# dv_analog_interface_ch_old.net
KiCad netlist of a schematic drawn in Altium Designer
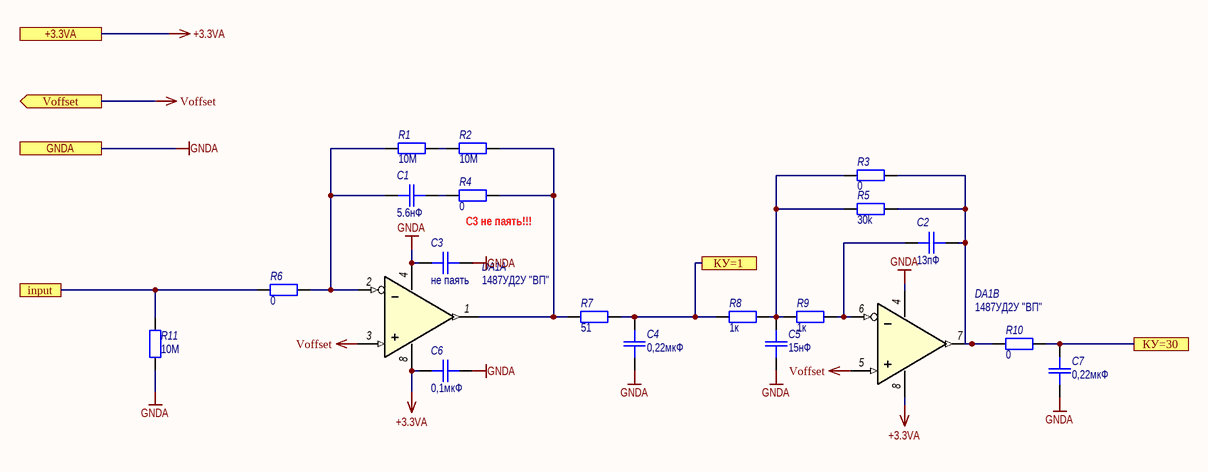
[diagram p0: dv_analog_interface_ch_old.SchDoc]

(export (version "E")
  (design (tool "Eeschema 10.0.6"))
  (components
    (comp (ref "C1")
      (value "5.6нФ")
      (footprint "SMD_C0805")
      (description "Capacitor")
      (fields (field (name "Comment") "K10-79"))
      (libsource (lib "Passive") (part "Capacitor"))
    )
    (comp (ref "C2")
      (value "13пФ")
      (footprint "SMD_C0805")
      (description "Capacitor")
      (fields (field (name "Comment") "K10-79"))
      (libsource (lib "Passive") (part "Capacitor"))
    )
    (comp (ref "C3")
      (value "не паять")
      (footprint "SMD_C0805")
      (description "Capacitor")
      (fields (field (name "Comment") "K10-79"))
      (libsource (lib "Passive") (part "Capacitor"))
    )
    (comp (ref "C4")
      (value "0,22мкФ")
      (footprint "SMD_C0805")
      (description "Capacitor")
      (fields (field (name "Comment") "K10-79"))
      (libsource (lib "Passive") (part "Capacitor"))
    )
    (comp (ref "C5")
      (value "15нФ")
      (footprint "SMD_C0805")
      (description "Capacitor")
      (fields (field (name "Comment") "K10-79"))
      (libsource (lib "Passive") (part "Capacitor"))
    )
    (comp (ref "C6")
      (value "0,1мкФ")
      (footprint "SMD_C0805")
      (description "Capacitor")
      (fields (field (name "Comment") "K10-79"))
      (libsource (lib "Passive") (part "Capacitor"))
    )
    (comp (ref "C7")
      (value "0,22мкФ")
      (footprint "SMD_C0805")
      (description "Capacitor")
      (fields (field (name "Comment") "K10-79"))
      (libsource (lib "Passive") (part "Capacitor"))
    )
    (comp (ref "DA1")
      (value "1487UD2U")
      (footprint "HO2.8-1B")
      (description "Сдвоенный операционный усилитель")
      (fields (field (name "НАИМЕНОВАНИЕ") "1487УД2У \"ВП\""))
      (libsource (lib "1487UD2U") (part "1487UD2U"))
    )
    (comp (ref "R1")
      (value "10M")
      (footprint "SMD_0805")
      (description "Resistor")
      (fields (field (name "Comment") "OSM R1-12"))
      (libsource (lib "Passive") (part "Resistor"))
    )
    (comp (ref "R2")
      (value "10M")
      (footprint "SMD_0805")
      (description "Resistor")
      (fields (field (name "Comment") "OSM R1-12"))
      (libsource (lib "Passive") (part "Resistor"))
    )
    (comp (ref "R3")
      (value "0")
      (footprint "SMD_0805")
      (description "Resistor")
      (fields (field (name "Comment") "OSM R1-12"))
      (libsource (lib "Passive") (part "Resistor"))
    )
    (comp (ref "R4")
      (value "0")
      (footprint "SMD_0805")
      (description "Resistor")
      (fields (field (name "Comment") "OSM R1-12"))
      (libsource (lib "Passive") (part "Resistor"))
    )
    (comp (ref "R5")
      (value "30k")
      (footprint "SMD_0805")
      (description "Resistor")
      (fields (field (name "Comment") "OSM R1-12"))
      (libsource (lib "Passive") (part "Resistor"))
    )
    (comp (ref "R6")
      (value "0")
      (footprint "SMD_0805")
      (description "Resistor")
      (fields (field (name "Comment") "OSM R1-12"))
      (libsource (lib "Passive") (part "Resistor"))
    )
    (comp (ref "R7")
      (value "51")
      (footprint "SMD_0805")
      (description "Resistor")
      (fields (field (name "Comment") "OSM R1-12"))
      (libsource (lib "Passive") (part "Resistor"))
    )
    (comp (ref "R8")
      (value "1к")
      (footprint "SMD_0805")
      (description "Resistor")
      (fields (field (name "Comment") "OSM R1-12"))
      (libsource (lib "Passive") (part "Resistor"))
    )
    (comp (ref "R9")
      (value "1к")
      (footprint "SMD_0805")
      (description "Resistor")
      (fields (field (name "Comment") "OSM R1-12"))
      (libsource (lib "Passive") (part "Resistor"))
    )
    (comp (ref "R10")
      (value "0")
      (footprint "SMD_0805")
      (description "Resistor")
      (fields (field (name "Comment") "OSM R1-12"))
      (libsource (lib "Passive") (part "Resistor"))
    )
    (comp (ref "R11")
      (value "10M")
      (footprint "SMD_0805")
      (description "Resistor")
      (fields (field (name "Comment") "OSM R1-12"))
      (libsource (lib "") (part "Resistor_1"))
    )
  )
  (nets
    (net (code "1") (name "+3.3VA") (class "Default")
      (node (ref "C6") (pin "1") (pinfunction "1_1") (pintype "passive"))
      (node (ref "DA1") (pin "8") (pinfunction "Vss+_8") (pintype "passive"))
    )
    (net (code "2") (name "/input") (class "Default")
      (node (ref "R11") (pin "2") (pinfunction "2_2") (pintype "passive"))
      (node (ref "R6") (pin "1") (pinfunction "1_1") (pintype "passive"))
    )
    (net (code "3") (name "/КУ=1") (class "Default")
      (node (ref "C4") (pin "2") (pinfunction "2_2") (pintype "passive"))
      (node (ref "R7") (pin "2") (pinfunction "2_2") (pintype "passive"))
      (node (ref "R8") (pin "1") (pinfunction "1_1") (pintype "passive"))
    )
    (net (code "4") (name "/КУ=30") (class "Default")
      (node (ref "C7") (pin "2") (pinfunction "2_2") (pintype "passive"))
      (node (ref "R10") (pin "2") (pinfunction "2_2") (pintype "passive"))
    )
    (net (code "5") (name "GNDA") (class "Default")
      (node (ref "C3") (pin "1") (pinfunction "1_1") (pintype "passive"))
      (node (ref "C3") (pin "2") (pinfunction "2_2") (pintype "passive"))
      (node (ref "C4") (pin "1") (pinfunction "1_1") (pintype "passive"))
      (node (ref "C5") (pin "1") (pinfunction "1_1") (pintype "passive"))
      (node (ref "C6") (pin "2") (pinfunction "2_2") (pintype "passive"))
      (node (ref "C7") (pin "1") (pinfunction "1_1") (pintype "passive"))
      (node (ref "DA1") (pin "4") (pinfunction "Vss-_4") (pintype "passive"))
      (node (ref "R11") (pin "1") (pinfunction "1_1") (pintype "passive"))
    )
    (net (code "6") (name "Net-(C1-Pad2)") (class "Default")
      (node (ref "C1") (pin "2") (pinfunction "2_2") (pintype "passive"))
      (node (ref "R4") (pin "1") (pinfunction "1_1") (pintype "passive"))
    )
    (net (code "7") (name "Net-(C5-Pad2)") (class "Default")
      (node (ref "C5") (pin "2") (pinfunction "2_2") (pintype "passive"))
      (node (ref "R3") (pin "1") (pinfunction "1_1") (pintype "passive"))
      (node (ref "R5") (pin "1") (pinfunction "1_1") (pintype "passive"))
      (node (ref "R8") (pin "2") (pinfunction "2_2") (pintype "passive"))
      (node (ref "R9") (pin "1") (pinfunction "1_1") (pintype "passive"))
    )
    (net (code "8") (name "Net-(DA1A-In-)") (class "Default")
      (node (ref "C1") (pin "1") (pinfunction "1_1") (pintype "passive"))
      (node (ref "DA1") (pin "2") (pinfunction "In-_2") (pintype "input"))
      (node (ref "R1") (pin "1") (pinfunction "1_1") (pintype "passive"))
      (node (ref "R6") (pin "2") (pinfunction "2_2") (pintype "passive"))
    )
    (net (code "9") (name "Net-(DA1A-Out)") (class "Default")
      (node (ref "DA1") (pin "1") (pinfunction "Out_1") (pintype "output"))
      (node (ref "R2") (pin "2") (pinfunction "2_2") (pintype "passive"))
      (node (ref "R4") (pin "2") (pinfunction "2_2") (pintype "passive"))
      (node (ref "R7") (pin "1") (pinfunction "1_1") (pintype "passive"))
    )
    (net (code "10") (name "Net-(DA1B-In-)") (class "Default")
      (node (ref "C2") (pin "2") (pinfunction "2_2") (pintype "passive"))
      (node (ref "DA1") (pin "6") (pinfunction "In-_6") (pintype "input"))
      (node (ref "R9") (pin "2") (pinfunction "2_2") (pintype "passive"))
    )
    (net (code "11") (name "Net-(DA1B-Out)") (class "Default")
      (node (ref "C2") (pin "1") (pinfunction "1_1") (pintype "passive"))
      (node (ref "DA1") (pin "7") (pinfunction "Out_7") (pintype "output"))
      (node (ref "R10") (pin "1") (pinfunction "1_1") (pintype "passive"))
      (node (ref "R3") (pin "2") (pinfunction "2_2") (pintype "passive"))
      (node (ref "R5") (pin "2") (pinfunction "2_2") (pintype "passive"))
    )
    (net (code "12") (name "Net-(R1-Pad2)") (class "Default")
      (node (ref "R1") (pin "2") (pinfunction "2_2") (pintype "passive"))
      (node (ref "R2") (pin "1") (pinfunction "1_1") (pintype "passive"))
    )
    (net (code "13") (name "Voffset") (class "Default")
      (node (ref "DA1") (pin "3") (pinfunction "In+_3") (pintype "input"))
      (node (ref "DA1") (pin "5") (pinfunction "In+_5") (pintype "input"))
    )
  )
)
